# Heatedbed.net
KiCad netlist of a schematic drawn in Altium Designer
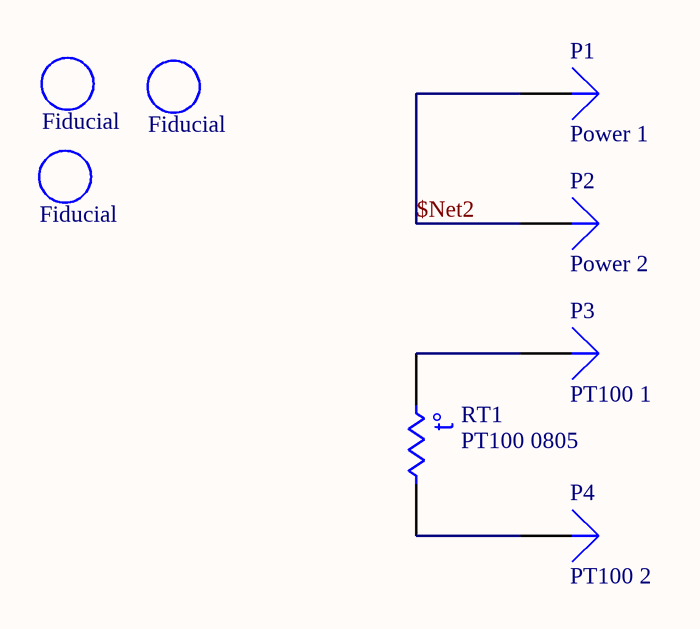
[diagram p0: Heatedbed.SchDoc]

(export (version "E")
  (design (tool "Eeschema 10.0.6"))
  (components
    (comp (ref "Fid1")
      (value "Fiducial")
      (footprint "Fiducial")
      (libsource (lib "Database_Faber") (part "Fiducial"))
    )
    (comp (ref "Fid2")
      (value "Fiducial")
      (footprint "Fiducial")
      (libsource (lib "Database_Faber") (part "Fiducial"))
    )
    (comp (ref "Fid3")
      (value "Fiducial")
      (footprint "Fiducial")
      (libsource (lib "Database_Faber") (part "Fiducial"))
    )
    (comp (ref "P1")
      (value "Power 1")
      (footprint "AVX Poke home contact")
      (description "Plug")
      (fields (field (name "MFG") "AVX") (field (name "PUBLISHER") "Altium Limited"))
      (libsource (lib "Miscellaneous Connectors") (part "Plug"))
    )
    (comp (ref "P2")
      (value "Power 2")
      (footprint "AVX Poke home contact")
      (description "Plug")
      (fields (field (name "MFG") "AVX") (field (name "PUBLISHER") "Altium Limited"))
      (libsource (lib "Miscellaneous Connectors") (part "Plug"))
    )
    (comp (ref "P3")
      (value "PT100 1")
      (footprint "AVX POKE HOME CONTACT 3MM")
      (description "Plug")
      (fields (field (name "MFG") "AVX") (field (name "PUBLISHER") "Altium Limited"))
      (libsource (lib "Miscellaneous Connectors") (part "Plug"))
    )
    (comp (ref "P4")
      (value "PT100 2")
      (footprint "AVX POKE HOME CONTACT 3MM")
      (description "Plug")
      (fields (field (name "MFG") "AVX") (field (name "PUBLISHER") "Altium Limited"))
      (libsource (lib "Miscellaneous Connectors") (part "Plug"))
    )
    (comp (ref "RT1")
      (value "PT100 0805")
      (footprint "6-0805_M")
      (description "Thermistor")
      (fields
        (field (name "MFG") "IST INNOVATIVE SENSOR TECHNOLOGY")
        (field (name "PUBLISHER") "Altium Limited")
      )
      (libsource (lib "Miscellaneous Devices") (part "Res Thermal"))
    )
  )
  (nets
    (net (code "1") (name "/$Net2") (class "Default")
      (node (ref "P1") (pin "1") (pinfunction "1_1") (pintype "passive"))
      (node (ref "P2") (pin "1") (pinfunction "1_1") (pintype "passive"))
    )
    (net (code "2") (name "Net-(P3-Pad1)") (class "Default")
      (node (ref "P3") (pin "1") (pinfunction "1_1") (pintype "passive"))
      (node (ref "RT1") (pin "1") (pinfunction "1_1") (pintype "passive"))
    )
    (net (code "3") (name "Net-(P4-Pad1)") (class "Default")
      (node (ref "P4") (pin "1") (pinfunction "1_1") (pintype "passive"))
      (node (ref "RT1") (pin "2") (pinfunction "2_2") (pintype "passive"))
    )
  )
)
